# 1_TOP.net
KiCad netlist of a schematic drawn in Altium Designer
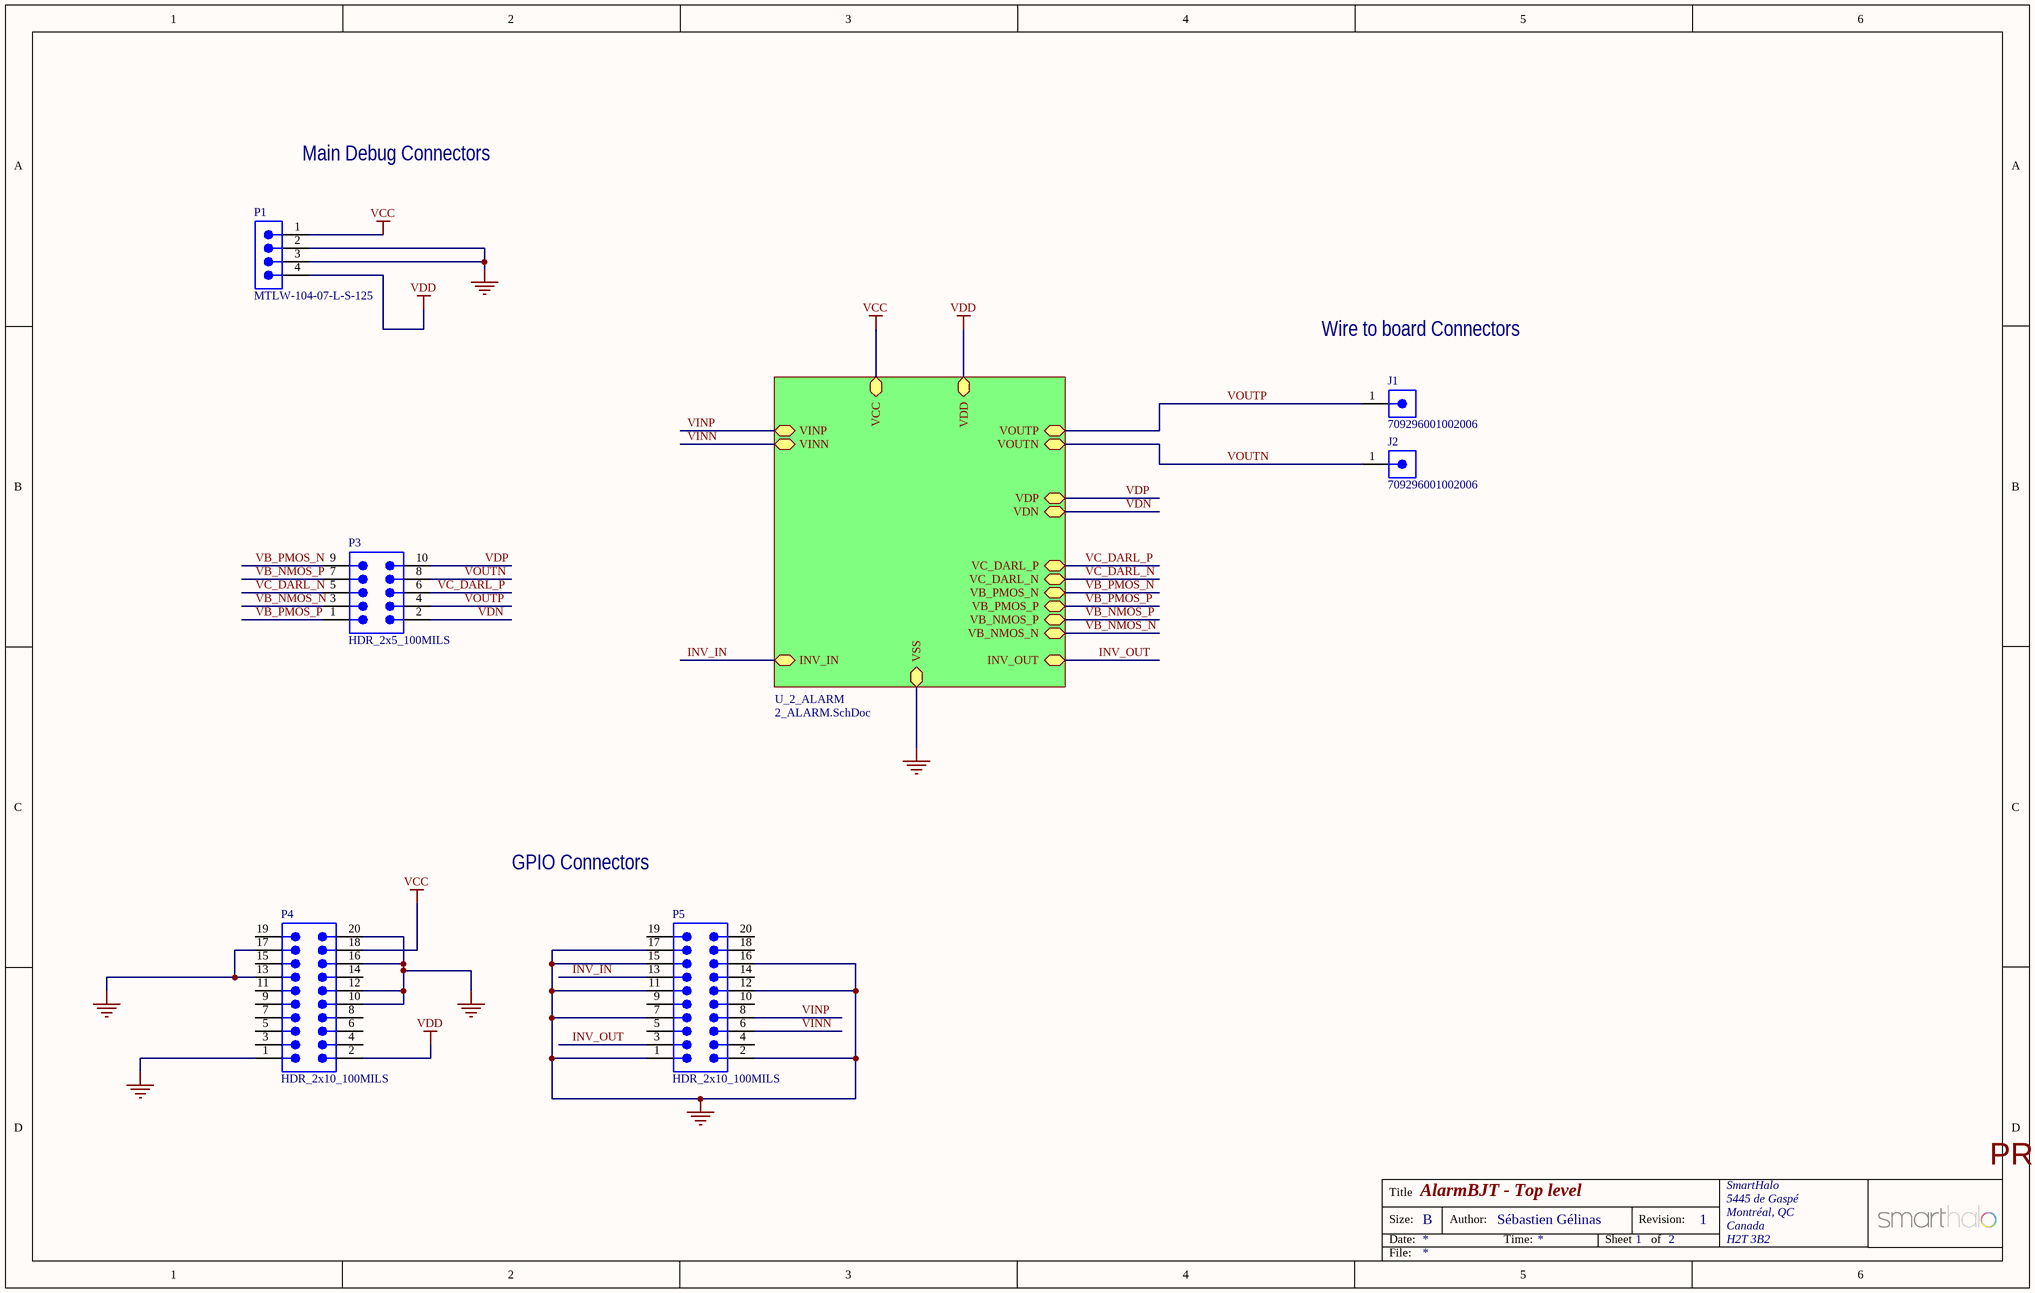
[diagram p0: 1_TOP.SchDoc]

(export (version "E")
  (design (tool "Eeschema 10.0.6"))
  (components
    (comp (ref "J1")
      (value "709296001002006")
      (footprint "709296001002006")
      (description "Connector, Single Horizontal Contact, 2 x 2 mm")
      (fields (field (name "MANUFACTURER") "AVX"))
      (libsource (lib "SmartHalo") (part "709296001002006"))
    )
    (comp (ref "J2")
      (value "709296001002006")
      (footprint "709296001002006")
      (description "Connector, Single Horizontal Contact, 2 x 2 mm")
      (fields (field (name "MANUFACTURER") "AVX"))
      (libsource (lib "SmartHalo") (part "709296001002006"))
    )
    (comp (ref "P1")
      (value "MTLW-104-07-L-S-125")
      (footprint "SMTC-MTLW-104-07-X-S-125")
      (fields (field (name "MANUFACTURER") "Samtec"))
      (libsource (lib "SmartHalo") (part "SMTC-MTLW-104-07-X-S-125"))
    )
    (comp (ref "P3")
      (value "HDR_2x5_100MILS")
      (footprint "HDR_2X5_100MILS")
      (description "Header, 100 mils, 2 rows, 10 pins")
      (libsource (lib "SmartHalo") (part "HDR_2x5_100MILS"))
    )
    (comp (ref "P4")
      (value "HDR_2x10_100MILS")
      (footprint "HDR_2X10_100MILS")
      (description "Header, 100 mils, 2 rows, 20 pins")
      (libsource (lib "SmartHalo") (part "HDR_2x10_100MILS"))
    )
    (comp (ref "P5")
      (value "HDR_2x10_100MILS")
      (footprint "HDR_2X10_100MILS")
      (description "Header, 100 mils, 2 rows, 20 pins")
      (libsource (lib "SmartHalo") (part "HDR_2x10_100MILS"))
    )
  )
  (nets
    (net (code "1") (name "/INV_IN") (class "Default")
      (node (ref "P5") (pin "13") (pinfunction "13_13") (pintype "passive"))
    )
    (net (code "2") (name "/INV_OUT") (class "Default")
      (node (ref "P5") (pin "3") (pinfunction "3_3") (pintype "passive"))
    )
    (net (code "3") (name "/VB_NMOS_N") (class "Default")
      (node (ref "P3") (pin "3") (pinfunction "3_3") (pintype "passive"))
    )
    (net (code "4") (name "/VB_NMOS_P") (class "Default")
      (node (ref "P3") (pin "7") (pinfunction "7_7") (pintype "passive"))
    )
    (net (code "5") (name "/VB_PMOS_N") (class "Default")
      (node (ref "P3") (pin "9") (pinfunction "9_9") (pintype "passive"))
    )
    (net (code "6") (name "/VB_PMOS_P") (class "Default")
      (node (ref "P3") (pin "1") (pinfunction "1_1") (pintype "passive"))
    )
    (net (code "7") (name "/VC_DARL_N") (class "Default")
      (node (ref "P3") (pin "5") (pinfunction "5_5") (pintype "passive"))
    )
    (net (code "8") (name "/VC_DARL_P") (class "Default")
      (node (ref "P3") (pin "6") (pinfunction "6_6") (pintype "passive"))
    )
    (net (code "9") (name "/VDN") (class "Default")
      (node (ref "P3") (pin "2") (pinfunction "2_2") (pintype "passive"))
    )
    (net (code "10") (name "/VDP") (class "Default")
      (node (ref "P3") (pin "10") (pinfunction "10_10") (pintype "passive"))
    )
    (net (code "11") (name "/VINN") (class "Default")
      (node (ref "P5") (pin "6") (pinfunction "6_6") (pintype "passive"))
    )
    (net (code "12") (name "/VINP") (class "Default")
      (node (ref "P5") (pin "8") (pinfunction "8_8") (pintype "passive"))
    )
    (net (code "13") (name "/VOUTN") (class "Default")
      (node (ref "J2") (pin "1") (pinfunction "1_1") (pintype "passive"))
      (node (ref "P3") (pin "8") (pinfunction "8_8") (pintype "passive"))
    )
    (net (code "14") (name "/VOUTP") (class "Default")
      (node (ref "J1") (pin "1") (pinfunction "1_1") (pintype "passive"))
      (node (ref "P3") (pin "4") (pinfunction "4_4") (pintype "passive"))
    )
    (net (code "15") (name "GND") (class "Default")
      (node (ref "P1") (pin "2") (pinfunction "2_2") (pintype "passive"))
      (node (ref "P1") (pin "3") (pinfunction "3_3") (pintype "passive"))
      (node (ref "P4") (pin "1") (pinfunction "1_1") (pintype "passive"))
      (node (ref "P4") (pin "10") (pinfunction "10_10") (pintype "passive"))
      (node (ref "P4") (pin "12") (pinfunction "12_12") (pintype "passive"))
      (node (ref "P4") (pin "13") (pinfunction "13_13") (pintype "passive"))
      (node (ref "P4") (pin "16") (pinfunction "16_16") (pintype "passive"))
      (node (ref "P4") (pin "17") (pinfunction "17_17") (pintype "passive"))
      (node (ref "P4") (pin "20") (pinfunction "20_20") (pintype "passive"))
      (node (ref "P5") (pin "1") (pinfunction "1_1") (pintype "passive"))
      (node (ref "P5") (pin "11") (pinfunction "11_11") (pintype "passive"))
      (node (ref "P5") (pin "12") (pinfunction "12_12") (pintype "passive"))
      (node (ref "P5") (pin "15") (pinfunction "15_15") (pintype "passive"))
      (node (ref "P5") (pin "16") (pinfunction "16_16") (pintype "passive"))
      (node (ref "P5") (pin "17") (pinfunction "17_17") (pintype "passive"))
      (node (ref "P5") (pin "2") (pinfunction "2_2") (pintype "passive"))
      (node (ref "P5") (pin "7") (pinfunction "7_7") (pintype "passive"))
    )
    (net (code "16") (name "VCC") (class "Default")
      (node (ref "P1") (pin "1") (pinfunction "1_1") (pintype "passive"))
      (node (ref "P4") (pin "18") (pinfunction "18_18") (pintype "passive"))
    )
    (net (code "17") (name "VDD") (class "Default")
      (node (ref "P1") (pin "4") (pinfunction "4_4") (pintype "passive"))
      (node (ref "P4") (pin "2") (pinfunction "2_2") (pintype "passive"))
    )
    (net (code "18") (name "unconnected-(P4-Pad3)") (class "Default")
      (node (ref "P4") (pin "3") (pinfunction "3_3") (pintype "passive"))
    )
    (net (code "19") (name "unconnected-(P4-Pad4)") (class "Default")
      (node (ref "P4") (pin "4") (pinfunction "4_4") (pintype "passive"))
    )
    (net (code "20") (name "unconnected-(P4-Pad5)") (class "Default")
      (node (ref "P4") (pin "5") (pinfunction "5_5") (pintype "passive"))
    )
    (net (code "21") (name "unconnected-(P4-Pad6)") (class "Default")
      (node (ref "P4") (pin "6") (pinfunction "6_6") (pintype "passive"))
    )
    (net (code "22") (name "unconnected-(P4-Pad7)") (class "Default")
      (node (ref "P4") (pin "7") (pinfunction "7_7") (pintype "passive"))
    )
    (net (code "23") (name "unconnected-(P4-Pad8)") (class "Default")
      (node (ref "P4") (pin "8") (pinfunction "8_8") (pintype "passive"))
    )
    (net (code "24") (name "unconnected-(P4-Pad9)") (class "Default")
      (node (ref "P4") (pin "9") (pinfunction "9_9") (pintype "passive"))
    )
    (net (code "25") (name "unconnected-(P4-Pad11)") (class "Default")
      (node (ref "P4") (pin "11") (pinfunction "11_11") (pintype "passive"))
    )
    (net (code "26") (name "unconnected-(P4-Pad14)") (class "Default")
      (node (ref "P4") (pin "14") (pinfunction "14_14") (pintype "passive"))
    )
    (net (code "27") (name "unconnected-(P4-Pad15)") (class "Default")
      (node (ref "P4") (pin "15") (pinfunction "15_15") (pintype "passive"))
    )
    (net (code "28") (name "unconnected-(P4-Pad19)") (class "Default")
      (node (ref "P4") (pin "19") (pinfunction "19_19") (pintype "passive"))
    )
    (net (code "29") (name "unconnected-(P5-Pad4)") (class "Default")
      (node (ref "P5") (pin "4") (pinfunction "4_4") (pintype "passive"))
    )
    (net (code "30") (name "unconnected-(P5-Pad5)") (class "Default")
      (node (ref "P5") (pin "5") (pinfunction "5_5") (pintype "passive"))
    )
    (net (code "31") (name "unconnected-(P5-Pad9)") (class "Default")
      (node (ref "P5") (pin "9") (pinfunction "9_9") (pintype "passive"))
    )
    (net (code "32") (name "unconnected-(P5-Pad10)") (class "Default")
      (node (ref "P5") (pin "10") (pinfunction "10_10") (pintype "passive"))
    )
    (net (code "33") (name "unconnected-(P5-Pad14)") (class "Default")
      (node (ref "P5") (pin "14") (pinfunction "14_14") (pintype "passive"))
    )
    (net (code "34") (name "unconnected-(P5-Pad18)") (class "Default")
      (node (ref "P5") (pin "18") (pinfunction "18_18") (pintype "passive"))
    )
    (net (code "35") (name "unconnected-(P5-Pad19)") (class "Default")
      (node (ref "P5") (pin "19") (pinfunction "19_19") (pintype "passive"))
    )
    (net (code "36") (name "unconnected-(P5-Pad20)") (class "Default")
      (node (ref "P5") (pin "20") (pinfunction "20_20") (pintype "passive"))
    )
  )
)
